# Power_LEDs.net
KiCad netlist of a schematic drawn in Altium Designer
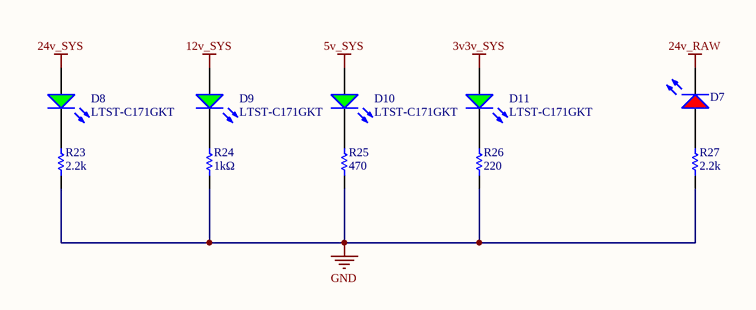
[diagram p0: Power_LEDs.SchDoc]

(export (version "E")
  (design (tool "Eeschema 10.0.6"))
  (components
    (comp (ref "D7")
      (value "Lite-On LTST-C170CKT")
      (footprint "PCB-divvmvv5iwnkp0y4rvhb-1")
      (description "LED; SMD; 0805; red; 2.8-10mcd; 2x1.25x1.1mm; 130°; 1.8÷2.4V; 10mA")
      (libsource (lib "CommunityVault") (part "SYM-b6f07ff2f0206937-1"))
    )
    (comp (ref "D8")
      (value "SYM-3aeff3ed7c74e528-12")
      (footprint "PCB-divvmvv5iwnkp0y4rvhb-1")
      (description "LED; SMD; 0805; green; 1.8-6mcd; 2x1.25x0.8mm; 130°; 2.1÷2.4V; 10mA")
      (fields (field (name "MANUFACTURER PART NUMBER") "LTST-C171GKT"))
      (libsource (lib "CommunityVault") (part "CMP-1544858-16"))
    )
    (comp (ref "D9")
      (value "SYM-3aeff3ed7c74e528-12")
      (footprint "PCB-divvmvv5iwnkp0y4rvhb-1")
      (description "LED; SMD; 0805; green; 1.8-6mcd; 2x1.25x0.8mm; 130°; 2.1÷2.4V; 10mA")
      (fields (field (name "MANUFACTURER PART NUMBER") "LTST-C171GKT"))
      (libsource (lib "CommunityVault") (part "CMP-1544858-16"))
    )
    (comp (ref "D10")
      (value "SYM-3aeff3ed7c74e528-12")
      (footprint "PCB-divvmvv5iwnkp0y4rvhb-1")
      (description "LED; SMD; 0805; green; 1.8-6mcd; 2x1.25x0.8mm; 130°; 2.1÷2.4V; 10mA")
      (fields (field (name "MANUFACTURER PART NUMBER") "LTST-C171GKT"))
      (libsource (lib "CommunityVault") (part "CMP-1544858-16"))
    )
    (comp (ref "D11")
      (value "SYM-3aeff3ed7c74e528-12")
      (footprint "PCB-divvmvv5iwnkp0y4rvhb-1")
      (description "LED; SMD; 0805; green; 1.8-6mcd; 2x1.25x0.8mm; 130°; 2.1÷2.4V; 10mA")
      (fields (field (name "MANUFACTURER PART NUMBER") "LTST-C171GKT"))
      (libsource (lib "CommunityVault") (part "CMP-1544858-16"))
    )
    (comp (ref "R23")
      (value "Res1")
      (footprint "RESC1508X06N")
      (description "RMCF Series 0603 0.1 W 2.2 kOhm ±1 % ±100 ppm/°C SMT Thick Film Chip Resistor")
      (fields (field (name "MANUFACTURER PART NUMBER") "RMCF0603FT2K20") (field (name "RESISTANCE") "2.2k"))
      (libsource (lib "CommunityVault") (part "CMP-49e581ca47bd9622-1"))
    )
    (comp (ref "R24")
      (value "Res1")
      (footprint "RESC1508X06N")
      (description "RMCF Series 0603 0.1 W 2.2 kOhm ±1 % ±100 ppm/°C SMT Thick Film Chip Resistor")
      (fields (field (name "MANUFACTURER PART NUMBER") "RMCF0603FT2K20") (field (name "RESISTANCE") "1kΩ"))
      (libsource (lib "CommunityVault") (part "CMP-49e581ca47bd9622-1"))
    )
    (comp (ref "R25")
      (value "Res1")
      (footprint "RESC1508X06N")
      (description "RMCF Series 0603 0.1 W 2.2 kOhm ±1 % ±100 ppm/°C SMT Thick Film Chip Resistor")
      (fields (field (name "MANUFACTURER PART NUMBER") "RMCF0603FT2K20") (field (name "RESISTANCE") "470"))
      (libsource (lib "CommunityVault") (part "CMP-49e581ca47bd9622-1"))
    )
    (comp (ref "R26")
      (value "Res1")
      (footprint "RESC1508X06N")
      (description "RMCF Series 0603 0.1 W 2.2 kOhm ±1 % ±100 ppm/°C SMT Thick Film Chip Resistor")
      (fields (field (name "MANUFACTURER PART NUMBER") "RMCF0603FT2K20") (field (name "RESISTANCE") "220"))
      (libsource (lib "CommunityVault") (part "CMP-49e581ca47bd9622-1"))
    )
    (comp (ref "R27")
      (value "Res1")
      (footprint "RESC1508X06N")
      (description "RMCF Series 0603 0.1 W 2.2 kOhm ±1 % ±100 ppm/°C SMT Thick Film Chip Resistor")
      (fields (field (name "MANUFACTURER PART NUMBER") "RMCF0603FT2K20") (field (name "RESISTANCE") "2.2k"))
      (libsource (lib "CommunityVault") (part "CMP-49e581ca47bd9622-1"))
    )
  )
  (nets
    (net (code "1") (name "3v3v_SYS") (class "Default")
      (node (ref "D11") (pin "2") (pinfunction "A_2") (pintype "passive"))
    )
    (net (code "2") (name "5v_SYS") (class "Default")
      (node (ref "D10") (pin "2") (pinfunction "A_2") (pintype "passive"))
    )
    (net (code "3") (name "12v_SYS") (class "Default")
      (node (ref "D9") (pin "2") (pinfunction "A_2") (pintype "passive"))
    )
    (net (code "4") (name "24v_RAW") (class "Default")
      (node (ref "D7") (pin "1") (pinfunction "C_1") (pintype "passive"))
    )
    (net (code "5") (name "24v_SYS") (class "Default")
      (node (ref "D8") (pin "2") (pinfunction "A_2") (pintype "passive"))
    )
    (net (code "6") (name "GND") (class "Default")
      (node (ref "R23") (pin "2") (pinfunction "2_2") (pintype "passive"))
      (node (ref "R24") (pin "2") (pinfunction "2_2") (pintype "passive"))
      (node (ref "R25") (pin "2") (pinfunction "2_2") (pintype "passive"))
      (node (ref "R26") (pin "2") (pinfunction "2_2") (pintype "passive"))
      (node (ref "R27") (pin "2") (pinfunction "2_2") (pintype "passive"))
    )
    (net (code "7") (name "Net-(D7-A)") (class "Default")
      (node (ref "D7") (pin "2") (pinfunction "A_2") (pintype "passive"))
      (node (ref "R27") (pin "1") (pinfunction "1_1") (pintype "passive"))
    )
    (net (code "8") (name "Net-(D8-C)") (class "Default")
      (node (ref "D8") (pin "1") (pinfunction "C_1") (pintype "passive"))
      (node (ref "R23") (pin "1") (pinfunction "1_1") (pintype "passive"))
    )
    (net (code "9") (name "Net-(D9-C)") (class "Default")
      (node (ref "D9") (pin "1") (pinfunction "C_1") (pintype "passive"))
      (node (ref "R24") (pin "1") (pinfunction "1_1") (pintype "passive"))
    )
    (net (code "10") (name "Net-(D10-C)") (class "Default")
      (node (ref "D10") (pin "1") (pinfunction "C_1") (pintype "passive"))
      (node (ref "R25") (pin "1") (pinfunction "1_1") (pintype "passive"))
    )
    (net (code "11") (name "Net-(D11-C)") (class "Default")
      (node (ref "D11") (pin "1") (pinfunction "C_1") (pintype "passive"))
      (node (ref "R26") (pin "1") (pinfunction "1_1") (pintype "passive"))
    )
  )
)
